# pcb_v2.net
KiCad netlist of a schematic drawn in EAGLE
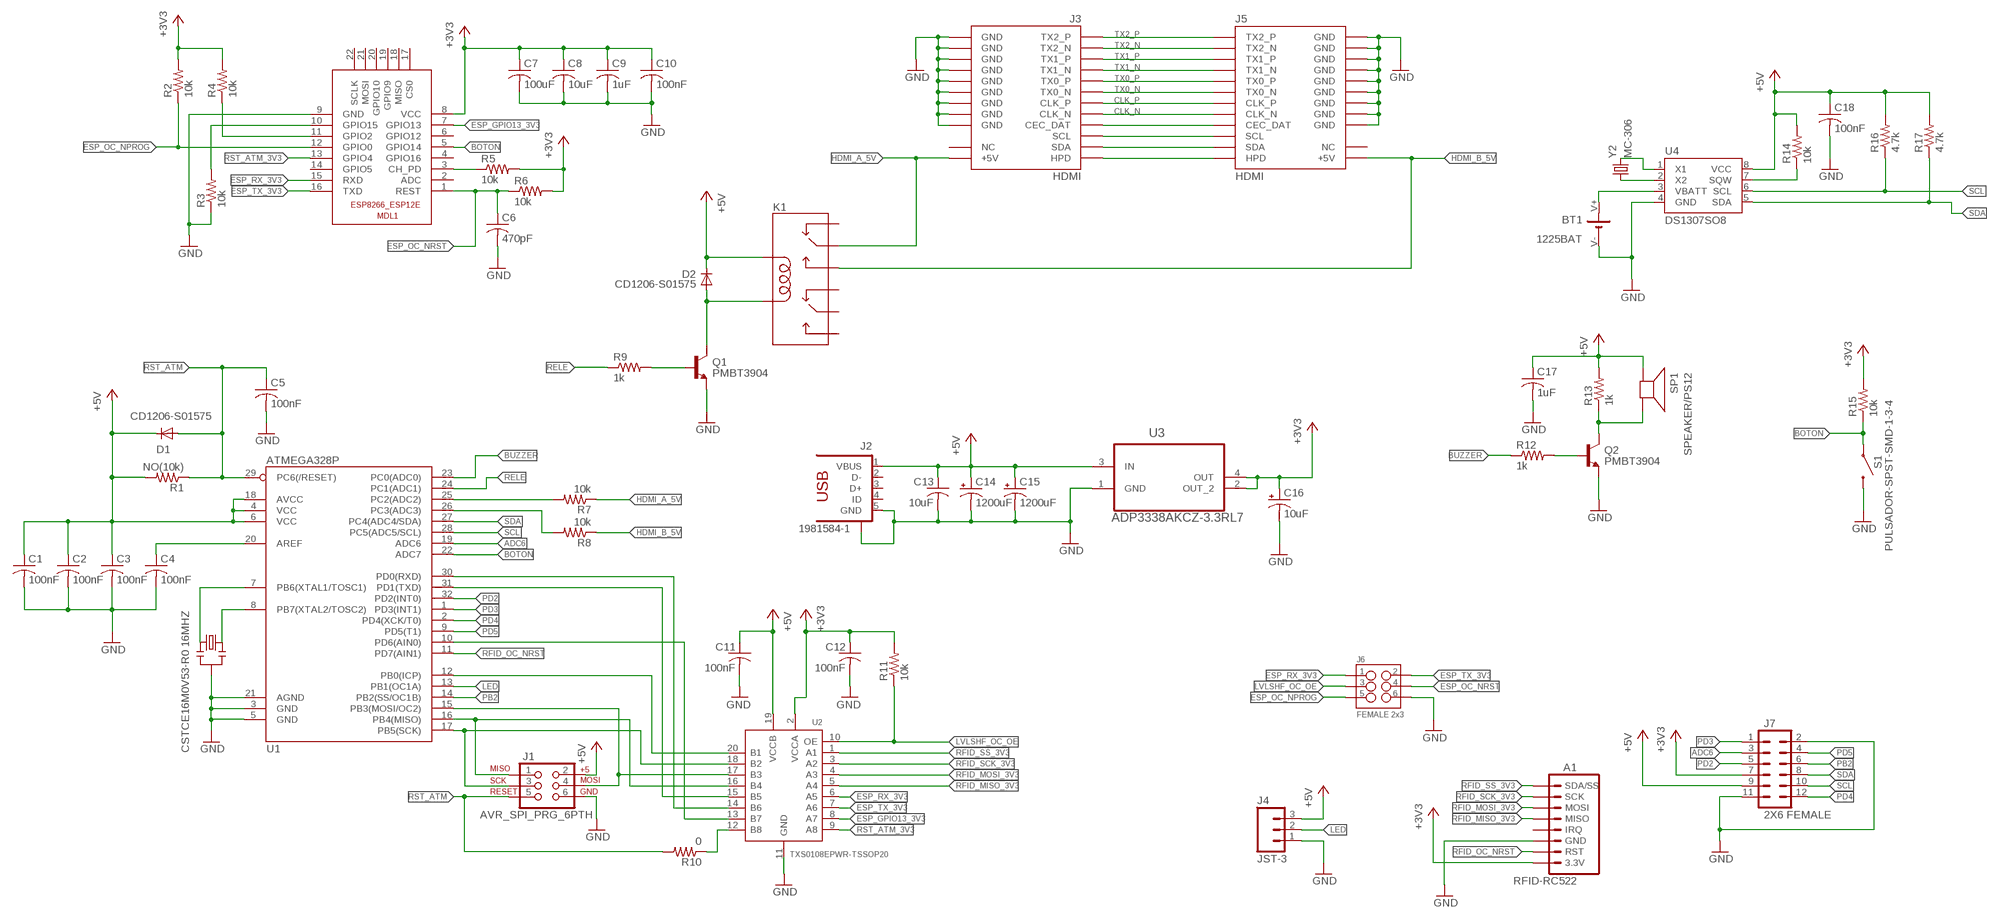
[diagram p0: schematic, sheet 1]

(export (version "E")
  (design (tool "Eeschema 10.0.6"))
  (components
    (comp (ref "A1")
      (value "RFID-RC522")
      (footprint "eagle-import:RFID-RC522")
      (libsource (lib "eagle-import") (part "RFID-RC522"))
    )
    (comp (ref "BT1")
      (value "1225BAT")
      (footprint "eagle-import:BHSD-1225-SM")
      (libsource (lib "eagle-import") (part "1225BAT"))
    )
    (comp (ref "C1")
      (value "100nF")
      (footprint "eagle-import:C0603")
      (libsource (lib "eagle-import") (part "C-USC0603"))
    )
    (comp (ref "C2")
      (value "100nF")
      (footprint "eagle-import:C0603")
      (libsource (lib "eagle-import") (part "C-USC0603"))
    )
    (comp (ref "C3")
      (value "100nF")
      (footprint "eagle-import:C0603")
      (libsource (lib "eagle-import") (part "C-USC0603"))
    )
    (comp (ref "C4")
      (value "100nF")
      (footprint "eagle-import:C0603")
      (libsource (lib "eagle-import") (part "C-USC0603"))
    )
    (comp (ref "C5")
      (value "100nF")
      (footprint "eagle-import:C0603")
      (libsource (lib "eagle-import") (part "C-USC0603"))
    )
    (comp (ref "C6")
      (value "470pF")
      (footprint "eagle-import:C0603")
      (libsource (lib "eagle-import") (part "C-USC0603"))
    )
    (comp (ref "C7")
      (value "100uF")
      (footprint "eagle-import:C1206")
      (libsource (lib "eagle-import") (part "C-USC1206"))
    )
    (comp (ref "C8")
      (value "10uF")
      (footprint "eagle-import:C0805")
      (libsource (lib "eagle-import") (part "C-USC0805"))
    )
    (comp (ref "C9")
      (value "1uF")
      (footprint "eagle-import:C0805")
      (libsource (lib "eagle-import") (part "C-USC0805"))
    )
    (comp (ref "C10")
      (value "100nF")
      (footprint "eagle-import:C0603")
      (libsource (lib "eagle-import") (part "C-USC0603"))
    )
    (comp (ref "C11")
      (value "100nF")
      (footprint "eagle-import:C0603")
      (libsource (lib "eagle-import") (part "C-USC0603"))
    )
    (comp (ref "C12")
      (value "100nF")
      (footprint "eagle-import:C0603")
      (libsource (lib "eagle-import") (part "C-USC0603"))
    )
    (comp (ref "C13")
      (value "10uF")
      (footprint "eagle-import:C0805")
      (libsource (lib "eagle-import") (part "C-USC0805"))
    )
    (comp (ref "C14")
      (value "1200uF")
      (footprint "eagle-import:UD-10X10_NICHICON")
      (libsource (lib "eagle-import") (part "CPOL-USUD-10X10"))
    )
    (comp (ref "C15")
      (value "1200uF")
      (footprint "eagle-import:UD-10X10_NICHICON")
      (libsource (lib "eagle-import") (part "CPOL-USUD-10X10"))
    )
    (comp (ref "C16")
      (value "10uF")
      (footprint "eagle-import:UD-5X5,8_NICHICON")
      (libsource (lib "eagle-import") (part "CPOL-USUD-5X5,8"))
    )
    (comp (ref "C17")
      (value "1uF")
      (footprint "eagle-import:C0805")
      (libsource (lib "eagle-import") (part "C-USC0805"))
    )
    (comp (ref "C18")
      (value "100nF")
      (footprint "eagle-import:C0603")
      (libsource (lib "eagle-import") (part "C-USC0603"))
    )
    (comp (ref "D1")
      (value "CD1206-S01575")
      (footprint "eagle-import:MINIMELF")
      (libsource (lib "eagle-import") (part "DIODE-MINIMELF"))
    )
    (comp (ref "D2")
      (value "CD1206-S01575")
      (footprint "eagle-import:MINIMELF")
      (libsource (lib "eagle-import") (part "DIODE-MINIMELF"))
    )
    (comp (ref "J1")
      (value "AVR_SPI_PRG_6PTH")
      (footprint "eagle-import:2X3")
      (libsource (lib "eagle-import") (part "AVR_SPI_PRG_6PTH"))
    )
    (comp (ref "J2")
      (value "1981584-1")
      (footprint "eagle-import:1981584-1")
      (libsource (lib "eagle-import") (part "1981584-1"))
    )
    (comp (ref "J3")
      (value "HDMI")
      (footprint "eagle-import:0471511071")
      (libsource (lib "eagle-import") (part "HDMI"))
    )
    (comp (ref "J4")
      (value "JST-3")
      (footprint "eagle-import:B3B-PH-SM4-TB")
      (libsource (lib "eagle-import") (part "JST-3"))
    )
    (comp (ref "J5")
      (value "HDMI")
      (footprint "eagle-import:0471511071")
      (libsource (lib "eagle-import") (part "HDMI"))
    )
    (comp (ref "J6")
      (value "FEMALE 2x3")
      (footprint "eagle-import:2X3")
      (libsource (lib "eagle-import") (part "M03X2FEMALE"))
    )
    (comp (ref "J7")
      (value "2X6 FEMALE")
      (footprint "eagle-import:2X6")
      (libsource (lib "eagle-import") (part "M06X2PTH_FEMALE"))
    )
    (comp (ref "K1")
      (value "RELAY_EE2")
      (footprint "eagle-import:RELAY-EE2")
      (libsource (lib "eagle-import") (part "RELAY_EE2"))
    )
    (comp (ref "MDL1")
      (value "ESP8266-12EESP8266-ESP12E")
      (footprint "eagle-import:ESP8266-ESP12E")
      (libsource (lib "eagle-import") (part "ESP8266-12EESP8266-ESP12E"))
    )
    (comp (ref "Q1")
      (value "PMBT3904")
      (footprint "eagle-import:SOT-23-3")
      (libsource (lib "eagle-import") (part "PMBT3904"))
    )
    (comp (ref "Q2")
      (value "PMBT3904")
      (footprint "eagle-import:SOT-23-3")
      (libsource (lib "eagle-import") (part "PMBT3904"))
    )
    (comp (ref "R1")
      (value "NO(10k)")
      (footprint "eagle-import:R0805")
      (libsource (lib "eagle-import") (part "R-US_R0805"))
    )
    (comp (ref "R2")
      (value "10k")
      (footprint "eagle-import:R0603")
      (libsource (lib "eagle-import") (part "R-US_R0603"))
    )
    (comp (ref "R3")
      (value "10k")
      (footprint "eagle-import:R0603")
      (libsource (lib "eagle-import") (part "R-US_R0603"))
    )
    (comp (ref "R4")
      (value "10k")
      (footprint "eagle-import:R0603")
      (libsource (lib "eagle-import") (part "R-US_R0603"))
    )
    (comp (ref "R5")
      (value "10k")
      (footprint "eagle-import:R0603")
      (libsource (lib "eagle-import") (part "R-US_R0603"))
    )
    (comp (ref "R6")
      (value "10k")
      (footprint "eagle-import:R0603")
      (libsource (lib "eagle-import") (part "R-US_R0603"))
    )
    (comp (ref "R7")
      (value "10k")
      (footprint "eagle-import:R0603")
      (libsource (lib "eagle-import") (part "R-US_R0603"))
    )
    (comp (ref "R8")
      (value "10k")
      (footprint "eagle-import:R0603")
      (libsource (lib "eagle-import") (part "R-US_R0603"))
    )
    (comp (ref "R9")
      (value "1k")
      (footprint "eagle-import:R0805")
      (libsource (lib "eagle-import") (part "R-US_R0805"))
    )
    (comp (ref "R10")
      (value "0")
      (footprint "eagle-import:R0805")
      (libsource (lib "eagle-import") (part "R-US_R0805"))
    )
    (comp (ref "R11")
      (value "10k")
      (footprint "eagle-import:R0603")
      (libsource (lib "eagle-import") (part "R-US_R0603"))
    )
    (comp (ref "R12")
      (value "1k")
      (footprint "eagle-import:R0805")
      (libsource (lib "eagle-import") (part "R-US_R0805"))
    )
    (comp (ref "R13")
      (value "1k")
      (footprint "eagle-import:R0805")
      (libsource (lib "eagle-import") (part "R-US_R0805"))
    )
    (comp (ref "R14")
      (value "10k")
      (footprint "eagle-import:R0603")
      (libsource (lib "eagle-import") (part "R-US_R0603"))
    )
    (comp (ref "R15")
      (value "10k")
      (footprint "eagle-import:R0603")
      (libsource (lib "eagle-import") (part "R-US_R0603"))
    )
    (comp (ref "R16")
      (value "4.7k")
      (footprint "eagle-import:R0603")
      (libsource (lib "eagle-import") (part "R-US_R0603"))
    )
    (comp (ref "R17")
      (value "4.7k")
      (footprint "eagle-import:R0603")
      (libsource (lib "eagle-import") (part "R-US_R0603"))
    )
    (comp (ref "S1")
      (value "PULSADOR-SPST-SMD-1-3-4")
      (footprint "eagle-import:PTS645SM43SMTR92")
      (libsource (lib "eagle-import") (part "PULSADOR-SPST-SMD-1-3-4"))
    )
    (comp (ref "SP1")
      (value "SPEAKER/PS12")
      (footprint "eagle-import:PS12")
      (libsource (lib "eagle-import") (part "SPEAKER/PS12"))
    )
    (comp (ref "U1")
      (value "ATMEGA328P")
      (footprint "eagle-import:TQFP32-08")
      (libsource (lib "eagle-import") (part "ATMEGA328_SMT"))
    )
    (comp (ref "U2")
      (value "TXS0108EPWR-TSSOP20")
      (footprint "eagle-import:TSSOP20-0.65-6.5X4.4MM")
      (fields (field (name "MPN") "TXS0108EPWR"))
      (libsource (lib "eagle-import") (part "LOGIC-TXS0108EPWR(TSSOP20)"))
    )
    (comp (ref "U3")
      (value "ADP3338AKCZ-3.3RL7")
      (footprint "eagle-import:SOT230P700X180-4N")
      (libsource (lib "eagle-import") (part "ADP3338AKCZ-3.3RL7"))
    )
    (comp (ref "U4")
      (value "DS1307SO8")
      (footprint "eagle-import:SO08")
      (libsource (lib "eagle-import") (part "DS1307SO8"))
    )
    (comp (ref "Y1")
      (value "CSTCE16M0V53-R0 16MHZ")
      (footprint "eagle-import:RESONATOR")
      (libsource (lib "eagle-import") (part "RESONATORMU"))
    )
    (comp (ref "Y2")
      (value "MC-306")
      (footprint "eagle-import:MC-306")
      (fields (field (name "MPN") "MC-306 60.0KHZ  100PPM ,12.5PF"))
      (libsource (lib "eagle-import") (part "MC-306"))
    )
  )
  (nets
    (net (code "1") (name "+3V3") (class "Default")
      (node (ref "A1") (pin "3.3V") (pinfunction "3.3V_3.3V") (pintype "passive"))
      (node (ref "C10") (pin "1") (pinfunction "1_1") (pintype "passive"))
      (node (ref "C12") (pin "1") (pinfunction "1_1") (pintype "passive"))
      (node (ref "C16") (pin "+") (pinfunction "+_+") (pintype "passive"))
      (node (ref "C7") (pin "1") (pinfunction "1_1") (pintype "passive"))
      (node (ref "C8") (pin "1") (pinfunction "1_1") (pintype "passive"))
      (node (ref "C9") (pin "1") (pinfunction "1_1") (pintype "passive"))
      (node (ref "J7") (pin "7") (pinfunction "7_7") (pintype "passive"))
      (node (ref "MDL1") (pin "8") (pinfunction "VCC_8") (pintype "bidirectional"))
      (node (ref "R11") (pin "2") (pinfunction "2_2") (pintype "passive"))
      (node (ref "R15") (pin "2") (pinfunction "2_2") (pintype "passive"))
      (node (ref "R2") (pin "2") (pinfunction "2_2") (pintype "passive"))
      (node (ref "R4") (pin "2") (pinfunction "2_2") (pintype "passive"))
      (node (ref "R5") (pin "2") (pinfunction "2_2") (pintype "passive"))
      (node (ref "R6") (pin "2") (pinfunction "2_2") (pintype "passive"))
      (node (ref "U2") (pin "2") (pinfunction "VCCA_2") (pintype "bidirectional"))
      (node (ref "U3") (pin "2") (pinfunction "OUT_2_2") (pintype "output"))
      (node (ref "U3") (pin "4") (pinfunction "OUT_4") (pintype "output"))
    )
    (net (code "2") (name "+5V") (class "Default")
      (node (ref "C1") (pin "1") (pinfunction "1_1") (pintype "passive"))
      (node (ref "C11") (pin "1") (pinfunction "1_1") (pintype "passive"))
      (node (ref "C13") (pin "1") (pinfunction "1_1") (pintype "passive"))
      (node (ref "C14") (pin "+") (pinfunction "+_+") (pintype "passive"))
      (node (ref "C15") (pin "+") (pinfunction "+_+") (pintype "passive"))
      (node (ref "C17") (pin "1") (pinfunction "1_1") (pintype "passive"))
      (node (ref "C18") (pin "1") (pinfunction "1_1") (pintype "passive"))
      (node (ref "C2") (pin "1") (pinfunction "1_1") (pintype "passive"))
      (node (ref "C3") (pin "1") (pinfunction "1_1") (pintype "passive"))
      (node (ref "D1") (pin "C") (pinfunction "C_C") (pintype "passive"))
      (node (ref "D2") (pin "C") (pinfunction "C_C") (pintype "passive"))
      (node (ref "J1") (pin "2") (pinfunction "2_2") (pintype "passive"))
      (node (ref "J2") (pin "1") (pinfunction "VBUS_1") (pintype "passive"))
      (node (ref "J4") (pin "3") (pinfunction "3_3") (pintype "passive"))
      (node (ref "J7") (pin "9") (pinfunction "9_9") (pintype "passive"))
      (node (ref "K1") (pin "1") (pinfunction "COIL+_1") (pintype "bidirectional"))
      (node (ref "R1") (pin "2") (pinfunction "2_2") (pintype "passive"))
      (node (ref "R13") (pin "2") (pinfunction "2_2") (pintype "passive"))
      (node (ref "R14") (pin "2") (pinfunction "2_2") (pintype "passive"))
      (node (ref "R16") (pin "2") (pinfunction "2_2") (pintype "passive"))
      (node (ref "R17") (pin "2") (pinfunction "2_2") (pintype "passive"))
      (node (ref "SP1") (pin "P$1") (pinfunction "+_P$1") (pintype "passive"))
      (node (ref "U1") (pin "18") (pinfunction "AVCC_18") (pintype "bidirectional"))
      (node (ref "U1") (pin "4") (pinfunction "VCC_4") (pintype "bidirectional"))
      (node (ref "U1") (pin "6") (pinfunction "VCC_6") (pintype "bidirectional"))
      (node (ref "U2") (pin "19") (pinfunction "VCCB_19") (pintype "bidirectional"))
      (node (ref "U3") (pin "3") (pinfunction "IN_3") (pintype "input"))
      (node (ref "U4") (pin "8") (pinfunction "VCC_8") (pintype "bidirectional"))
    )
    (net (code "3") (name "/CLK_N") (class "Default")
      (node (ref "J3") (pin "P$12") (pinfunction "CLK_N_P$12") (pintype "bidirectional"))
      (node (ref "J5") (pin "P$12") (pinfunction "CLK_N_P$12") (pintype "bidirectional"))
    )
    (net (code "4") (name "/CLK_P") (class "Default")
      (node (ref "J3") (pin "P$10") (pinfunction "CLK_P_P$10") (pintype "bidirectional"))
      (node (ref "J5") (pin "P$10") (pinfunction "CLK_P_P$10") (pintype "bidirectional"))
    )
    (net (code "5") (name "/TX0_N") (class "Default")
      (node (ref "J3") (pin "P$9") (pinfunction "TX0_N_P$9") (pintype "bidirectional"))
      (node (ref "J5") (pin "P$9") (pinfunction "TX0_N_P$9") (pintype "bidirectional"))
    )
    (net (code "6") (name "/TX0_P") (class "Default")
      (node (ref "J3") (pin "P$7") (pinfunction "TX0_P_P$7") (pintype "bidirectional"))
      (node (ref "J5") (pin "P$7") (pinfunction "TX0_P_P$7") (pintype "bidirectional"))
    )
    (net (code "7") (name "/TX1_N") (class "Default")
      (node (ref "J3") (pin "P$6") (pinfunction "TX1_N_P$6") (pintype "bidirectional"))
      (node (ref "J5") (pin "P$6") (pinfunction "TX1_N_P$6") (pintype "bidirectional"))
    )
    (net (code "8") (name "/TX1_P") (class "Default")
      (node (ref "J3") (pin "P$4") (pinfunction "TX1_P_P$4") (pintype "bidirectional"))
      (node (ref "J5") (pin "P$4") (pinfunction "TX1_P_P$4") (pintype "bidirectional"))
    )
    (net (code "9") (name "/TX2_N") (class "Default")
      (node (ref "J3") (pin "P$3") (pinfunction "TX2_N_P$3") (pintype "bidirectional"))
      (node (ref "J5") (pin "P$3") (pinfunction "TX2_N_P$3") (pintype "bidirectional"))
    )
    (net (code "10") (name "/TX2_P") (class "Default")
      (node (ref "J3") (pin "P$1") (pinfunction "TX2_P_P$1") (pintype "bidirectional"))
      (node (ref "J5") (pin "P$1") (pinfunction "TX2_P_P$1") (pintype "bidirectional"))
    )
    (net (code "11") (name "ADC6") (class "Default")
      (node (ref "J7") (pin "3") (pinfunction "3_3") (pintype "passive"))
      (node (ref "U1") (pin "19") (pinfunction "ADC6_19") (pintype "bidirectional"))
    )
    (net (code "12") (name "BOTON") (class "Default")
      (node (ref "MDL1") (pin "5") (pinfunction "GPIO14_5") (pintype "bidirectional"))
      (node (ref "R15") (pin "1") (pinfunction "1_1") (pintype "passive"))
      (node (ref "S1") (pin "P$1") (pinfunction "P$1_P$1") (pintype "passive"))
      (node (ref "U1") (pin "22") (pinfunction "ADC7_22") (pintype "bidirectional"))
    )
    (net (code "13") (name "BUZZER") (class "Default")
      (node (ref "R12") (pin "1") (pinfunction "1_1") (pintype "passive"))
      (node (ref "U1") (pin "23") (pinfunction "PC0(ADC0)_23") (pintype "bidirectional"))
    )
    (net (code "14") (name "ESP_GPIO13_3V3") (class "Default")
      (node (ref "MDL1") (pin "7") (pinfunction "GPIO13_7") (pintype "bidirectional"))
      (node (ref "U2") (pin "8") (pinfunction "A7_8") (pintype "bidirectional"))
    )
    (net (code "15") (name "ESP_OC_NPROG") (class "Default")
      (node (ref "J6") (pin "5") (pinfunction "5_5") (pintype "bidirectional"))
      (node (ref "MDL1") (pin "12") (pinfunction "GPIO0_12") (pintype "bidirectional"))
      (node (ref "R2") (pin "1") (pinfunction "1_1") (pintype "passive"))
    )
    (net (code "16") (name "ESP_OC_NRST") (class "Default")
      (node (ref "C6") (pin "1") (pinfunction "1_1") (pintype "passive"))
      (node (ref "J6") (pin "4") (pinfunction "4_4") (pintype "bidirectional"))
      (node (ref "MDL1") (pin "1") (pinfunction "REST_1") (pintype "bidirectional"))
      (node (ref "R6") (pin "1") (pinfunction "1_1") (pintype "passive"))
    )
    (net (code "17") (name "ESP_RX_3V3") (class "Default")
      (node (ref "J6") (pin "1") (pinfunction "1_1") (pintype "bidirectional"))
      (node (ref "MDL1") (pin "15") (pinfunction "RXD_15") (pintype "bidirectional"))
      (node (ref "U2") (pin "6") (pinfunction "A5_6") (pintype "bidirectional"))
    )
    (net (code "18") (name "ESP_TX_3V3") (class "Default")
      (node (ref "J6") (pin "2") (pinfunction "2_2") (pintype "bidirectional"))
      (node (ref "MDL1") (pin "16") (pinfunction "TXD_16") (pintype "bidirectional"))
      (node (ref "U2") (pin "7") (pinfunction "A6_7") (pintype "bidirectional"))
    )
    (net (code "19") (name "GND") (class "Default")
      (node (ref "A1") (pin "GND") (pinfunction "GND_GND") (pintype "passive"))
      (node (ref "BT1") (pin "V-") (pinfunction "V-_V-") (pintype "passive"))
      (node (ref "C1") (pin "2") (pinfunction "2_2") (pintype "passive"))
      (node (ref "C10") (pin "2") (pinfunction "2_2") (pintype "passive"))
      (node (ref "C11") (pin "2") (pinfunction "2_2") (pintype "passive"))
      (node (ref "C12") (pin "2") (pinfunction "2_2") (pintype "passive"))
      (node (ref "C13") (pin "2") (pinfunction "2_2") (pintype "passive"))
      (node (ref "C14") (pin "-") (pinfunction "-_-") (pintype "passive"))
      (node (ref "C15") (pin "-") (pinfunction "-_-") (pintype "passive"))
      (node (ref "C16") (pin "-") (pinfunction "-_-") (pintype "passive"))
      (node (ref "C17") (pin "2") (pinfunction "2_2") (pintype "passive"))
      (node (ref "C18") (pin "2") (pinfunction "2_2") (pintype "passive"))
      (node (ref "C2") (pin "2") (pinfunction "2_2") (pintype "passive"))
      (node (ref "C3") (pin "2") (pinfunction "2_2") (pintype "passive"))
      (node (ref "C4") (pin "2") (pinfunction "2_2") (pintype "passive"))
      (node (ref "C5") (pin "2") (pinfunction "2_2") (pintype "passive"))
      (node (ref "C6") (pin "2") (pinfunction "2_2") (pintype "passive"))
      (node (ref "C7") (pin "2") (pinfunction "2_2") (pintype "passive"))
      (node (ref "C8") (pin "2") (pinfunction "2_2") (pintype "passive"))
      (node (ref "C9") (pin "2") (pinfunction "2_2") (pintype "passive"))
      (node (ref "J1") (pin "6") (pinfunction "6_6") (pintype "passive"))
      (node (ref "J2") (pin "5") (pinfunction "GND_5") (pintype "passive"))
      (node (ref "J2") (pin "S1") (pinfunction "S1_S1") (pintype "passive"))
      (node (ref "J2") (pin "S2") (pinfunction "S2_S2") (pintype "passive"))
      (node (ref "J2") (pin "S3") (pinfunction "S3_S3") (pintype "passive"))
      (node (ref "J2") (pin "S4") (pinfunction "S4_S4") (pintype "passive"))
      (node (ref "J3") (pin "P$11") (pinfunction "GND_P$11") (pintype "bidirectional"))
      (node (ref "J3") (pin "P$17") (pinfunction "GND_P$17") (pintype "bidirectional"))
      (node (ref "J3") (pin "P$2") (pinfunction "GND_P$2") (pintype "bidirectional"))
      (node (ref "J3") (pin "P$20") (pinfunction "GND_P$20") (pintype "bidirectional"))
      (node (ref "J3") (pin "P$21") (pinfunction "GND_P$21") (pintype "bidirectional"))
      (node (ref "J3") (pin "P$22") (pinfunction "GND_P$22") (pintype "bidirectional"))
      (node (ref "J3") (pin "P$23") (pinfunction "GND_P$23") (pintype "bidirectional"))
      (node (ref "J3") (pin "P$5") (pinfunction "GND_P$5") (pintype "bidirectional"))
      (node (ref "J3") (pin "P$8") (pinfunction "GND_P$8") (pintype "bidirectional"))
      (node (ref "J4") (pin "1") (pinfunction "1_1") (pintype "passive"))
      (node (ref "J5") (pin "P$11") (pinfunction "GND_P$11") (pintype "bidirectional"))
      (node (ref "J5") (pin "P$17") (pinfunction "GND_P$17") (pintype "bidirectional"))
      (node (ref "J5") (pin "P$2") (pinfunction "GND_P$2") (pintype "bidirectional"))
      (node (ref "J5") (pin "P$20") (pinfunction "GND_P$20") (pintype "bidirectional"))
      (node (ref "J5") (pin "P$21") (pinfunction "GND_P$21") (pintype "bidirectional"))
      (node (ref "J5") (pin "P$22") (pinfunction "GND_P$22") (pintype "bidirectional"))
      (node (ref "J5") (pin "P$23") (pinfunction "GND_P$23") (pintype "bidirectional"))
      (node (ref "J5") (pin "P$5") (pinfunction "GND_P$5") (pintype "bidirectional"))
      (node (ref "J5") (pin "P$8") (pinfunction "GND_P$8") (pintype "bidirectional"))
      (node (ref "J6") (pin "6") (pinfunction "6_6") (pintype "bidirectional"))
      (node (ref "J7") (pin "11") (pinfunction "11_11") (pintype "passive"))
      (node (ref "J7") (pin "2") (pinfunction "2_2") (pintype "passive"))
      (node (ref "MDL1") (pin "9") (pinfunction "GND_9") (pintype "bidirectional"))
      (node (ref "Q1") (pin "2") (pinfunction "E_2") (pintype "passive"))
      (node (ref "Q2") (pin "2") (pinfunction "E_2") (pintype "passive"))
      (node (ref "R3") (pin "1") (pinfunction "1_1") (pintype "passive"))
      (node (ref "S1") (pin "P$3") (pinfunction "P$2_P$3") (pintype "passive"))
      (node (ref "S1") (pin "P$4") (pinfunction "P$2_P$4") (pintype "passive"))
      (node (ref "U1") (pin "21") (pinfunction "AGND_21") (pintype "bidirectional"))
      (node (ref "U1") (pin "3") (pinfunction "GND_3") (pintype "bidirectional"))
      (node (ref "U1") (pin "5") (pinfunction "GND_5") (pintype "bidirectional"))
      (node (ref "U2") (pin "11") (pinfunction "GND_11") (pintype "bidirectional"))
      (node (ref "U3") (pin "1") (pinfunction "GND_1") (pintype "passive"))
      (node (ref "U4") (pin "4") (pinfunction "GND_4") (pintype "bidirectional"))
      (node (ref "Y1") (pin "2") (pinfunction "2_2") (pintype "passive"))
    )
    (net (code "20") (name "HDMI_A_5V") (class "Default")
      (node (ref "J3") (pin "P$18") (pinfunction "+5V_P$18") (pintype "bidirectional"))
      (node (ref "K1") (pin "4") (pinfunction "MAIN1_4") (pintype "bidirectional"))
      (node (ref "R7") (pin "1") (pinfunction "1_1") (pintype "passive"))
    )
    (net (code "21") (name "HDMI_B_5V") (class "Default")
      (node (ref "J5") (pin "P$18") (pinfunction "+5V_P$18") (pintype "bidirectional"))
      (node (ref "K1") (pin "5") (pinfunction "OFF1_5") (pintype "bidirectional"))
      (node (ref "R8") (pin "1") (pinfunction "1_1") (pintype "passive"))
    )
    (net (code "22") (name "LED") (class "Default")
      (node (ref "J4") (pin "2") (pinfunction "2_2") (pintype "passive"))
      (node (ref "U1") (pin "13") (pinfunction "PB1(OC1A)_13") (pintype "bidirectional"))
    )
    (net (code "23") (name "LVLSHF_OC_OE") (class "Default")
      (node (ref "J6") (pin "3") (pinfunction "3_3") (pintype "bidirectional"))
      (node (ref "R11") (pin "1") (pinfunction "1_1") (pintype "passive"))
      (node (ref "U2") (pin "10") (pinfunction "OE_10") (pintype "bidirectional"))
    )
    (net (code "24") (name "Net-(J3-CEC_DAT)") (class "Default")
      (node (ref "J3") (pin "P$13") (pinfunction "CEC_DAT_P$13") (pintype "bidirectional"))
      (node (ref "J5") (pin "P$13") (pinfunction "CEC_DAT_P$13") (pintype "bidirectional"))
    )
    (net (code "25") (name "Net-(J3-HPD)") (class "Default")
      (node (ref "J3") (pin "P$19") (pinfunction "HPD_P$19") (pintype "bidirectional"))
      (node (ref "J5") (pin "P$19") (pinfunction "HPD_P$19") (pintype "bidirectional"))
    )
    (net (code "26") (name "Net-(J3-SCL)") (class "Default")
      (node (ref "J3") (pin "P$15") (pinfunction "SCL_P$15") (pintype "bidirectional"))
      (node (ref "J5") (pin "P$15") (pinfunction "SCL_P$15") (pintype "bidirectional"))
    )
    (net (code "27") (name "Net-(J3-SDA)") (class "Default")
      (node (ref "J3") (pin "P$16") (pinfunction "SDA_P$16") (pintype "bidirectional"))
      (node (ref "J5") (pin "P$16") (pinfunction "SDA_P$16") (pintype "bidirectional"))
    )
    (net (code "28") (name "Net-(K1-COIL-)") (class "Default")
      (node (ref "D2") (pin "A") (pinfunction "A_A") (pintype "passive"))
      (node (ref "K1") (pin "12") (pinfunction "COIL-_12") (pintype "bidirectional"))
      (node (ref "Q1") (pin "3") (pinfunction "C_3") (pintype "passive"))
    )
    (net (code "29") (name "Net-(MDL1-CH_PD)") (class "Default")
      (node (ref "MDL1") (pin "3") (pinfunction "CH_PD_3") (pintype "bidirectional"))
      (node (ref "R5") (pin "1") (pinfunction "1_1") (pintype "passive"))
    )
    (net (code "30") (name "Net-(MDL1-GPIO2)") (class "Default")
      (node (ref "MDL1") (pin "11") (pinfunction "GPIO2_11") (pintype "bidirectional"))
      (node (ref "R4") (pin "1") (pinfunction "1_1") (pintype "passive"))
    )
    (net (code "31") (name "Net-(MDL1-GPIO15)") (class "Default")
      (node (ref "MDL1") (pin "10") (pinfunction "GPIO15_10") (pintype "bidirectional"))
      (node (ref "R3") (pin "2") (pinfunction "2_2") (pintype "passive"))
    )
    (net (code "32") (name "Net-(Q1-B)") (class "Default")
      (node (ref "Q1") (pin "1") (pinfunction "B_1") (pintype "passive"))
      (node (ref "R9") (pin "2") (pinfunction "2_2") (pintype "passive"))
    )
    (net (code "33") (name "Net-(Q2-B)") (class "Default")
      (node (ref "Q2") (pin "1") (pinfunction "B_1") (pintype "passive"))
      (node (ref "R12") (pin "2") (pinfunction "2_2") (pintype "passive"))
    )
    (net (code "34") (name "Net-(Q2-C)") (class "Default")
      (node (ref "Q2") (pin "3") (pinfunction "C_3") (pintype "passive"))
      (node (ref "R13") (pin "1") (pinfunction "1_1") (pintype "passive"))
      (node (ref "SP1") (pin "P$2") (pinfunction "-_P$2") (pintype "passive"))
    )
    (net (code "35") (name "Net-(U1-AREF)") (class "Default")
      (node (ref "C4") (pin "1") (pinfunction "1_1") (pintype "passive"))
      (node (ref "U1") (pin "20") (pinfunction "AREF_20") (pintype "bidirectional"))
    )
    (net (code "36") (name "Net-(U1-PB0(ICP))") (class "Default")
      (node (ref "U1") (pin "12") (pinfunction "PB0(ICP)_12") (pintype "bidirectional"))
      (node (ref "U2") (pin "20") (pinfunction "B1_20") (pintype "bidirectional"))
    )
    (net (code "37") (name "Net-(U1-PB3(MOSI{slash}OC2))") (class "Default")
      (node (ref "J1") (pin "4") (pinfunction "4_4") (pintype "passive"))
      (node (ref "U1") (pin "15") (pinfunction "PB3(MOSI/OC2)_15") (pintype "bidirectional"))
      (node (ref "U2") (pin "17") (pinfunction "B3_17") (pintype "bidirectional"))
    )
    (net (code "38") (name "Net-(U1-PB4(MISO))") (class "Default")
      (node (ref "J1") (pin "1") (pinfunction "1_1") (pintype "passive"))
      (node (ref "U1") (pin "16") (pinfunction "PB4(MISO)_16") (pintype "bidirectional"))
      (node (ref "U2") (pin "16") (pinfunction "B4_16") (pintype "bidirectional"))
    )
    (net (code "39") (name "Net-(U1-PB5(SCK))") (class "Default")
      (node (ref "J1") (pin "3") (pinfunction "3_3") (pintype "passive"))
      (node (ref "U1") (pin "17") (pinfunction "PB5(SCK)_17") (pintype "bidirectional"))
      (node (ref "U2") (pin "18") (pinfunction "B2_18") (pintype "bidirectional"))
    )
    (net (code "40") (name "Net-(U1-PB6(XTAL1{slash}TOSC1))") (class "Default")
      (node (ref "U1") (pin "7") (pinfunction "PB6(XTAL1/TOSC1)_7") (pintype "bidirectional"))
      (node (ref "Y1") (pin "1") (pinfunction "1_1") (pintype "passive"))
    )
    (net (code "41") (name "Net-(U1-PB7(XTAL2{slash}TOSC2))") (class "Default")
      (node (ref "U1") (pin "8") (pinfunction "PB7(XTAL2/TOSC2)_8") (pintype "bidirectional"))
      (node (ref "Y1") (pin "3") (pinfunction "3_3") (pintype "passive"))
    )
    (net (code "42") (name "Net-(U1-PC2(ADC2))") (class "Default")
      (node (ref "R7") (pin "2") (pinfunction "2_2") (pintype "passive"))
      (node (ref "U1") (pin "25") (pinfunction "PC2(ADC2)_25") (pintype "bidirectional"))
    )
    (net (code "43") (name "Net-(U1-PC3(ADC3))") (class "Default")
      (node (ref "R8") (pin "2") (pinfunction "2_2") (pintype "passive"))
      (node (ref "U1") (pin "26") (pinfunction "PC3(ADC3)_26") (pintype "bidirectional"))
    )
    (net (code "44") (name "Net-(U1-PD0(RXD))") (class "Default")
      (node (ref "U1") (pin "30") (pinfunction "PD0(RXD)_30") (pintype "bidirectional"))
      (node (ref "U2") (pin "14") (pinfunction "B6_14") (pintype "bidirectional"))
    )
    (net (code "45") (name "Net-(U1-PD1(TXD))") (class "Default")
      (node (ref "U1") (pin "31") (pinfunction "PD1(TXD)_31") (pintype "bidirectional"))
      (node (ref "U2") (pin "15") (pinfunction "B5_15") (pintype "bidirectional"))
    )
    (net (code "46") (name "Net-(U1-PD6(AIN0))") (class "Default")
      (node (ref "U1") (pin "10") (pinfunction "PD6(AIN0)_10") (pintype "bidirectional"))
      (node (ref "U2") (pin "13") (pinfunction "B7_13") (pintype "bidirectional"))
    )
    (net (code "47") (name "Net-(U2-B8)") (class "Default")
      (node (ref "R10") (pin "1") (pinfunction "1_1") (pintype "passive"))
      (node (ref "U2") (pin "12") (pinfunction "B8_12") (pintype "bidirectional"))
    )
    (net (code "48") (name "Net-(U4-SQW)") (class "Default")
      (node (ref "R14") (pin "1") (pinfunction "1_1") (pintype "passive"))
      (node (ref "U4") (pin "7") (pinfunction "SQW_7") (pintype "bidirectional"))
    )
    (net (code "49") (name "Net-(U4-VBATT)") (class "Default")
      (node (ref "BT1") (pin "V+") (pinfunction "V+_V+") (pintype "passive"))
      (node (ref "U4") (pin "3") (pinfunction "VBATT_3") (pintype "bidirectional"))
    )
    (net (code "50") (name "Net-(U4-X1)") (class "Default")
      (node (ref "U4") (pin "1") (pinfunction "X1_1") (pintype "bidirectional"))
      (node (ref "Y2") (pin "4") (pinfunction "2_4") (pintype "passive"))
    )
    (net (code "51") (name "Net-(U4-X2)") (class "Default")
      (node (ref "U4") (pin "2") (pinfunction "X2_2") (pintype "bidirectional"))
      (node (ref "Y2") (pin "1") (pinfunction "1_1") (pintype "passive"))
    )
    (net (code "52") (name "PB2") (class "Default")
      (node (ref "J7") (pin "6") (pinfunction "6_6") (pintype "passive"))
      (node (ref "U1") (pin "14") (pinfunction "PB2(SS/OC1B)_14") (pintype "bidirectional"))
    )
    (net (code "53") (name "PD2") (class "Default")
      (node (ref "J7") (pin "5") (pinfunction "5_5") (pintype "passive"))
      (node (ref "U1") (pin "32") (pinfunction "PD2(INT0)_32") (pintype "bidirectional"))
    )
    (net (code "54") (name "PD3") (class "Default")
      (node (ref "J7") (pin "1") (pinfunction "1_1") (pintype "passive"))
      (node (ref "U1") (pin "1") (pinfunction "PD3(INT1)_1") (pintype "bidirectional"))
    )
    (net (code "55") (name "PD4") (class "Default")
      (node (ref "J7") (pin "12") (pinfunction "12_12") (pintype "passive"))
      (node (ref "U1") (pin "2") (pinfunction "PD4(XCK/T0)_2") (pintype "bidirectional"))
    )
    (net (code "56") (name "PD5") (class "Default")
      (node (ref "J7") (pin "4") (pinfunction "4_4") (pintype "passive"))
      (node (ref "U1") (pin "9") (pinfunction "PD5(T1)_9") (pintype "bidirectional"))
    )
    (net (code "57") (name "RELE") (class "Default")
      (node (ref "R9") (pin "1") (pinfunction "1_1") (pintype "passive"))
      (node (ref "U1") (pin "24") (pinfunction "PC1(ADC1)_24") (pintype "bidirectional"))
    )
    (net (code "58") (name "RFID_MISO_3V3") (class "Default")
      (node (ref "A1") (pin "MISO") (pinfunction "MISO_MISO") (pintype "passive"))
      (node (ref "U2") (pin "5") (pinfunction "A4_5") (pintype "bidirectional"))
    )
    (net (code "59") (name "RFID_MOSI_3V3") (class "Default")
      (node (ref "A1") (pin "MOSI") (pinfunction "MOSI_MOSI") (pintype "passive"))
      (node (ref "U2") (pin "4") (pinfunction "A3_4") (pintype "bidirectional"))
    )
    (net (code "60") (name "RFID_OC_NRST") (class "Default")
      (node (ref "A1") (pin "RST") (pinfunction "RST_RST") (pintype "passive"))
      (node (ref "U1") (pin "11") (pinfunction "PD7(AIN1)_11") (pintype "bidirectional"))
    )
    (net (code "61") (name "RFID_SCK_3V3") (class "Default")
      (node (ref "A1") (pin "SCK") (pinfunction "SCK_SCK") (pintype "passive"))
      (node (ref "U2") (pin "3") (pinfunction "A2_3") (pintype "bidirectional"))
    )
    (net (code "62") (name "RFID_SS_3V3") (class "Default")
      (node (ref "A1") (pin "SDA") (pinfunction "SDA/SS_SDA") (pintype "passive"))
      (node (ref "U2") (pin "1") (pinfunction "A1_1") (pintype "bidirectional"))
    )
    (net (code "63") (name "RST_ATM") (class "Default")
      (node (ref "C5") (pin "1") (pinfunction "1_1") (pintype "passive"))
      (node (ref "D1") (pin "A") (pinfunction "A_A") (pintype "passive"))
      (node (ref "J1") (pin "5") (pinfunction "5_5") (pintype "passive"))
      (node (ref "R1") (pin "1") (pinfunction "1_1") (pintype "passive"))
      (node (ref "R10") (pin "2") (pinfunction "2_2") (pintype "passive"))
      (node (ref "U1") (pin "29") (pinfunction "PC6(/RESET)_29") (pintype "bidirectional"))
    )
    (net (code "64") (name "RST_ATM_3V3") (class "Default")
      (node (ref "MDL1") (pin "13") (pinfunction "GPIO4_13") (pintype "bidirectional"))
      (node (ref "U2") (pin "9") (pinfunction "A8_9") (pintype "bidirectional"))
    )
    (net (code "65") (name "SCL") (class "Default")
      (node (ref "J7") (pin "10") (pinfunction "10_10") (pintype "passive"))
      (node (ref "R16") (pin "1") (pinfunction "1_1") (pintype "passive"))
      (node (ref "U1") (pin "28") (pinfunction "PC5(ADC5/SCL)_28") (pintype "bidirectional"))
      (node (ref "U4") (pin "6") (pinfunction "SCL_6") (pintype "bidirectional"))
    )
    (net (code "66") (name "SDA") (class "Default")
      (node (ref "J7") (pin "8") (pinfunction "8_8") (pintype "passive"))
      (node (ref "R17") (pin "1") (pinfunction "1_1") (pintype "passive"))
      (node (ref "U1") (pin "27") (pinfunction "PC4(ADC4/SDA)_27") (pintype "bidirectional"))
      (node (ref "U4") (pin "5") (pinfunction "SDA_5") (pintype "bidirectional"))
    )
    (net (code "67") (name "unconnected-(A1-PadIRQ)") (class "Default")
      (node (ref "A1") (pin "IRQ") (pinfunction "IRQ_IRQ") (pintype "passive"))
    )
    (net (code "68") (name "unconnected-(J2-D+-Pad3)") (class "Default")
      (node (ref "J2") (pin "3") (pinfunction "D+_3") (pintype "passive"))
    )
    (net (code "69") (name "unconnected-(J2-D--Pad2)") (class "Default")
      (node (ref "J2") (pin "2") (pinfunction "D-_2") (pintype "passive"))
    )
    (net (code "70") (name "unconnected-(J2-ID-Pad4)") (class "Default")
      (node (ref "J2") (pin "4") (pinfunction "ID_4") (pintype "passive"))
    )
    (net (code "71") (name "unconnected-(J3-NC-PadP$14)") (class "Default")
      (node (ref "J3") (pin "P$14") (pinfunction "NC_P$14") (pintype "bidirectional"))
    )
    (net (code "72") (name "unconnected-(J5-NC-PadP$14)") (class "Default")
      (node (ref "J5") (pin "P$14") (pinfunction "NC_P$14") (pintype "bidirectional"))
    )
    (net (code "73") (name "unconnected-(K1-MAIN2-Pad9)") (class "Default")
      (node (ref "K1") (pin "9") (pinfunction "MAIN2_9") (pintype "bidirectional"))
    )
    (net (code "74") (name "unconnected-(K1-OFF2-Pad8)") (class "Default")
      (node (ref "K1") (pin "8") (pinfunction "OFF2_8") (pintype "bidirectional"))
    )
    (net (code "75") (name "unconnected-(K1-ON1-Pad3)") (class "Default")
      (node (ref "K1") (pin "3") (pinfunction "ON1_3") (pintype "bidirectional"))
    )
    (net (code "76") (name "unconnected-(K1-ON2-Pad10)") (class "Default")
      (node (ref "K1") (pin "10") (pinfunction "ON2_10") (pintype "bidirectional"))
    )
    (net (code "77") (name "unconnected-(MDL1-ADC-Pad2)") (class "Default")
      (node (ref "MDL1") (pin "2") (pinfunction "ADC_2") (pintype "bidirectional"))
    )
    (net (code "78") (name "unconnected-(MDL1-CS0-Pad17)") (class "Default")
      (node (ref "MDL1") (pin "17") (pinfunction "CS0_17") (pintype "bidirectional"))
    )
    (net (code "79") (name "unconnected-(MDL1-GPIO5-Pad14)") (class "Default")
      (node (ref "MDL1") (pin "14") (pinfunction "GPIO5_14") (pintype "bidirectional"))
    )
    (net (code "80") (name "unconnected-(MDL1-GPIO9-Pad19)") (class "Default")
      (node (ref "MDL1") (pin "19") (pinfunction "GPIO9_19") (pintype "bidirectional"))
    )
    (net (code "81") (name "unconnected-(MDL1-GPIO10-Pad20)") (class "Default")
      (node (ref "MDL1") (pin "20") (pinfunction "GPIO10_20") (pintype "bidirectional"))
    )
    (net (code "82") (name "unconnected-(MDL1-GPIO12-Pad6)") (class "Default")
      (node (ref "MDL1") (pin "6") (pinfunction "GPIO12_6") (pintype "bidirectional"))
    )
    (net (code "83") (name "unconnected-(MDL1-GPIO16-Pad4)") (class "Default")
      (node (ref "MDL1") (pin "4") (pinfunction "GPIO16_4") (pintype "bidirectional"))
    )
    (net (code "84") (name "unconnected-(MDL1-MISO-Pad18)") (class "Default")
      (node (ref "MDL1") (pin "18") (pinfunction "MISO_18") (pintype "bidirectional"))
    )
    (net (code "85") (name "unconnected-(MDL1-MOSI-Pad21)") (class "Default")
      (node (ref "MDL1") (pin "21") (pinfunction "MOSI_21") (pintype "bidirectional"))
    )
    (net (code "86") (name "unconnected-(MDL1-SCLK-Pad22)") (class "Default")
      (node (ref "MDL1") (pin "22") (pinfunction "SCLK_22") (pintype "bidirectional"))
    )
  )
)
